# EVALBOARD_001.net
KiCad netlist of a schematic drawn in EAGLE
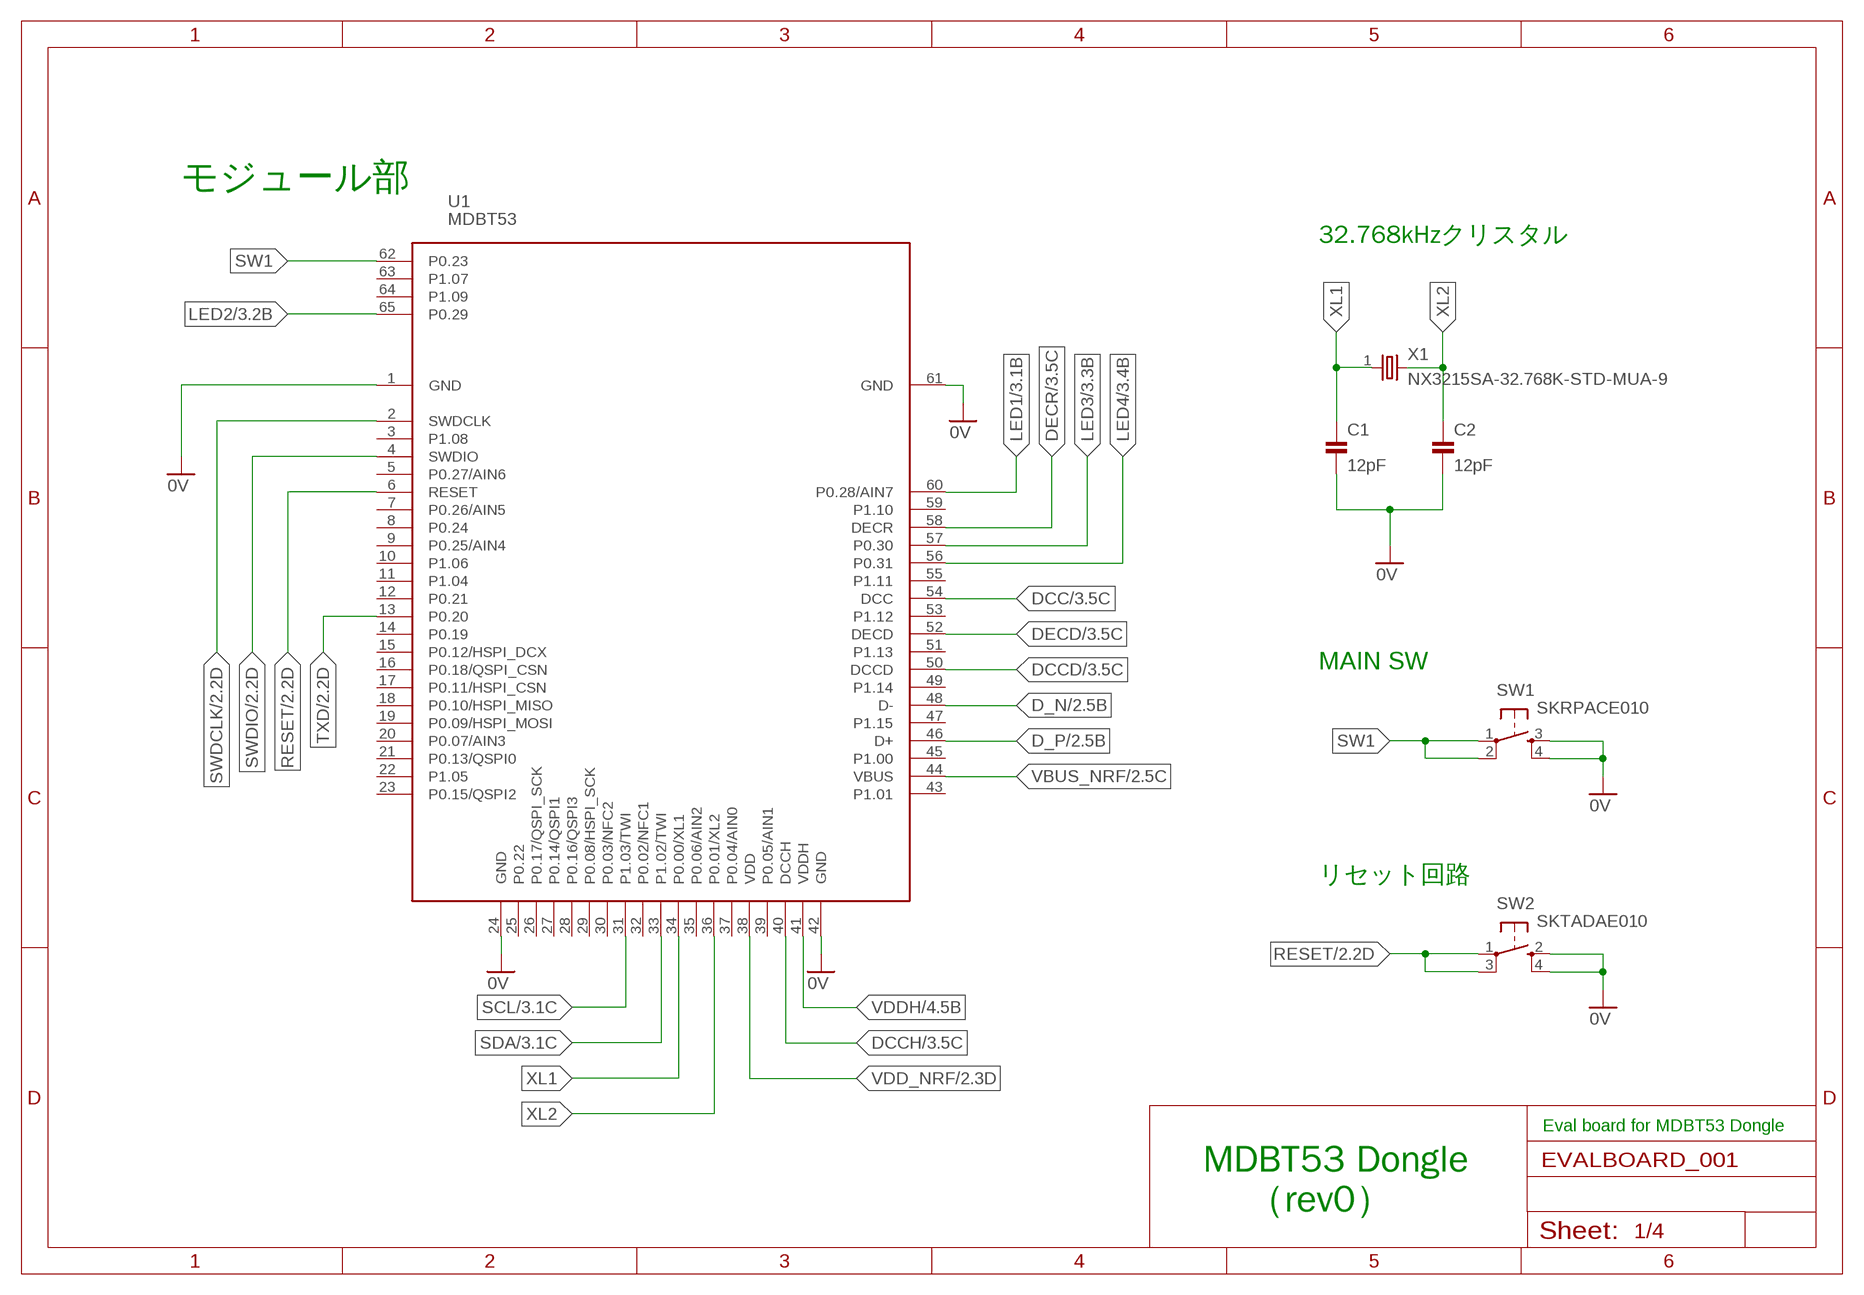
[diagram p0: schematic, sheet 1]
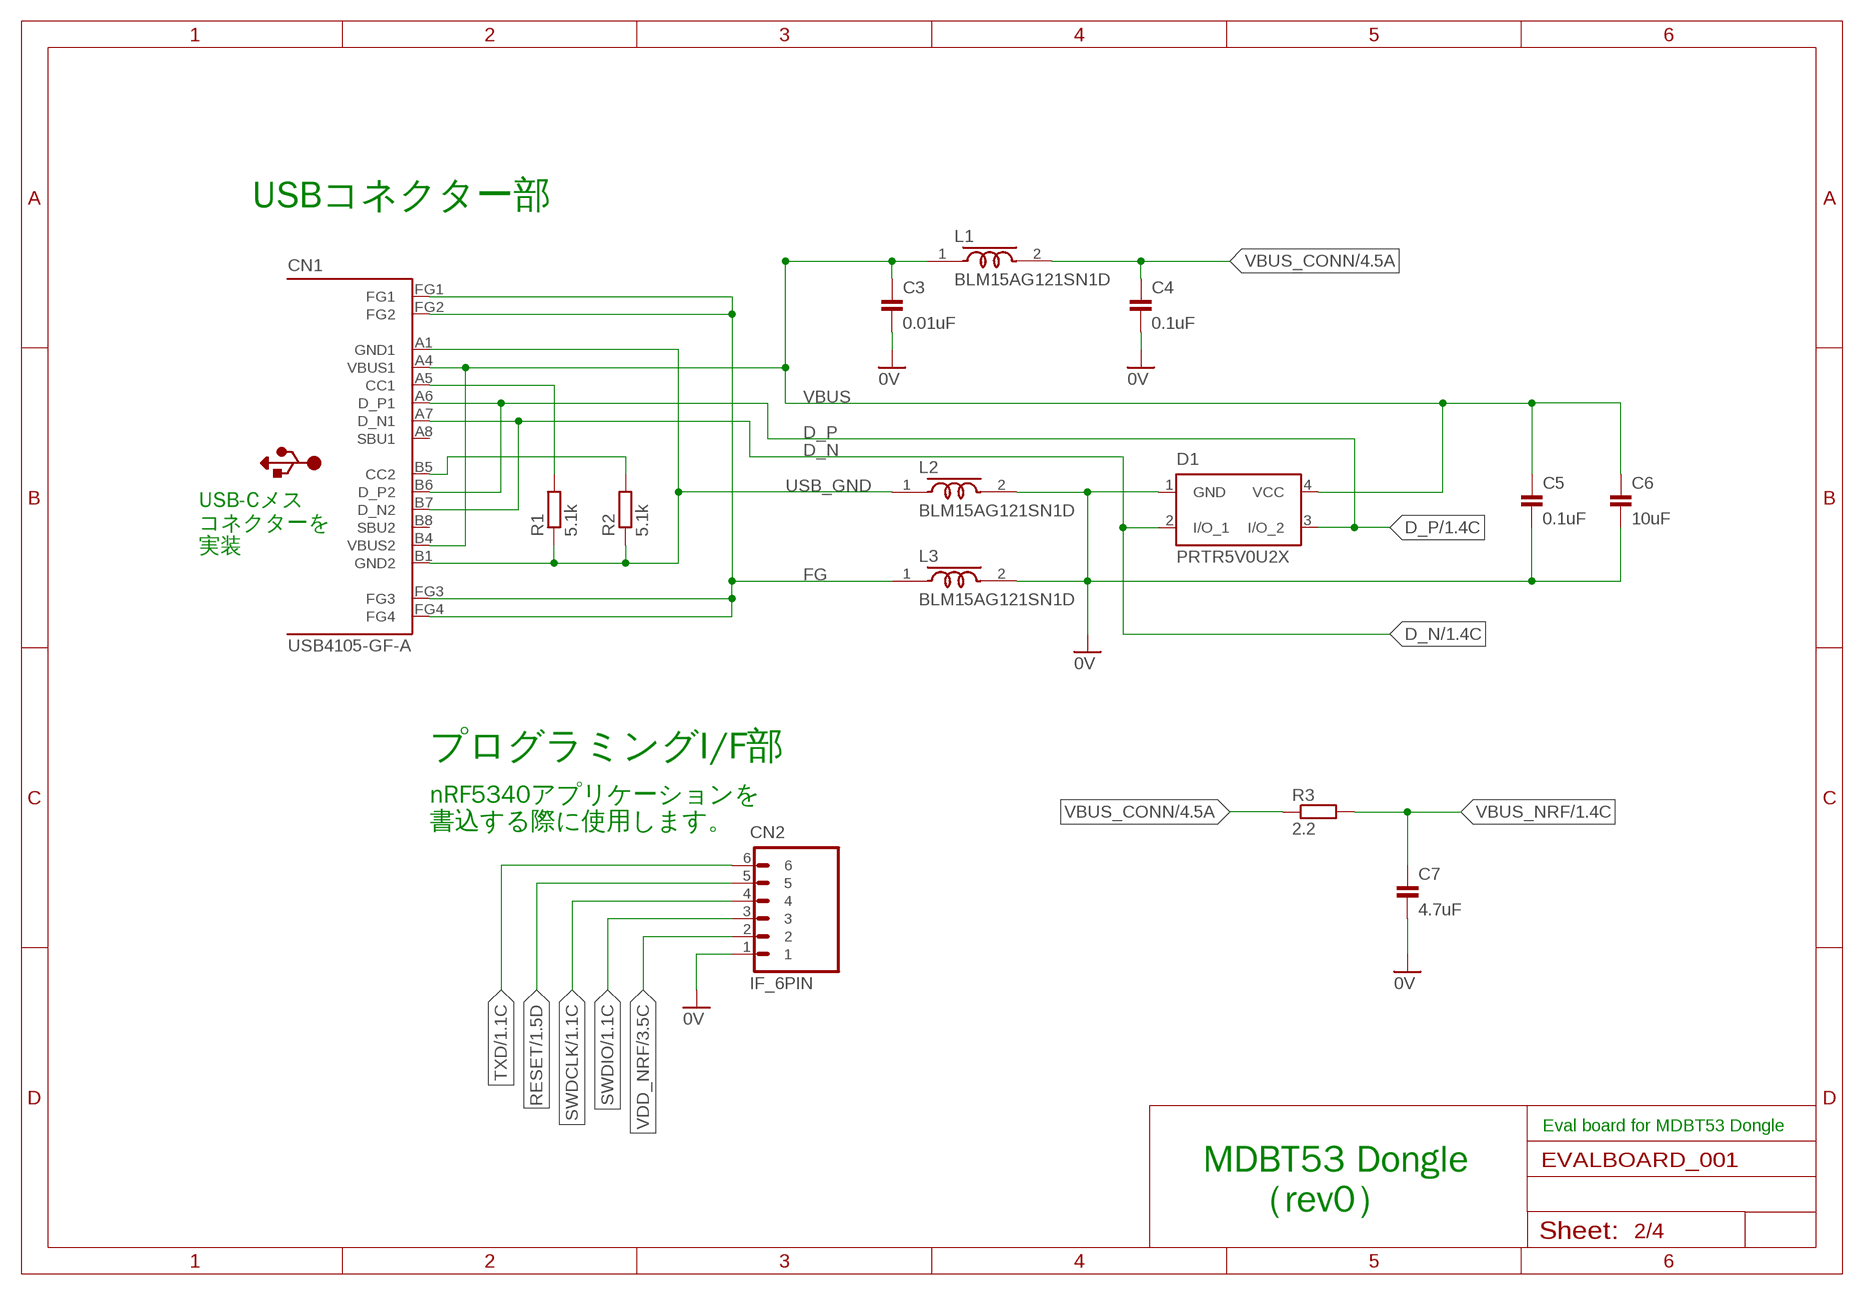
[diagram p1: schematic, sheet 2]
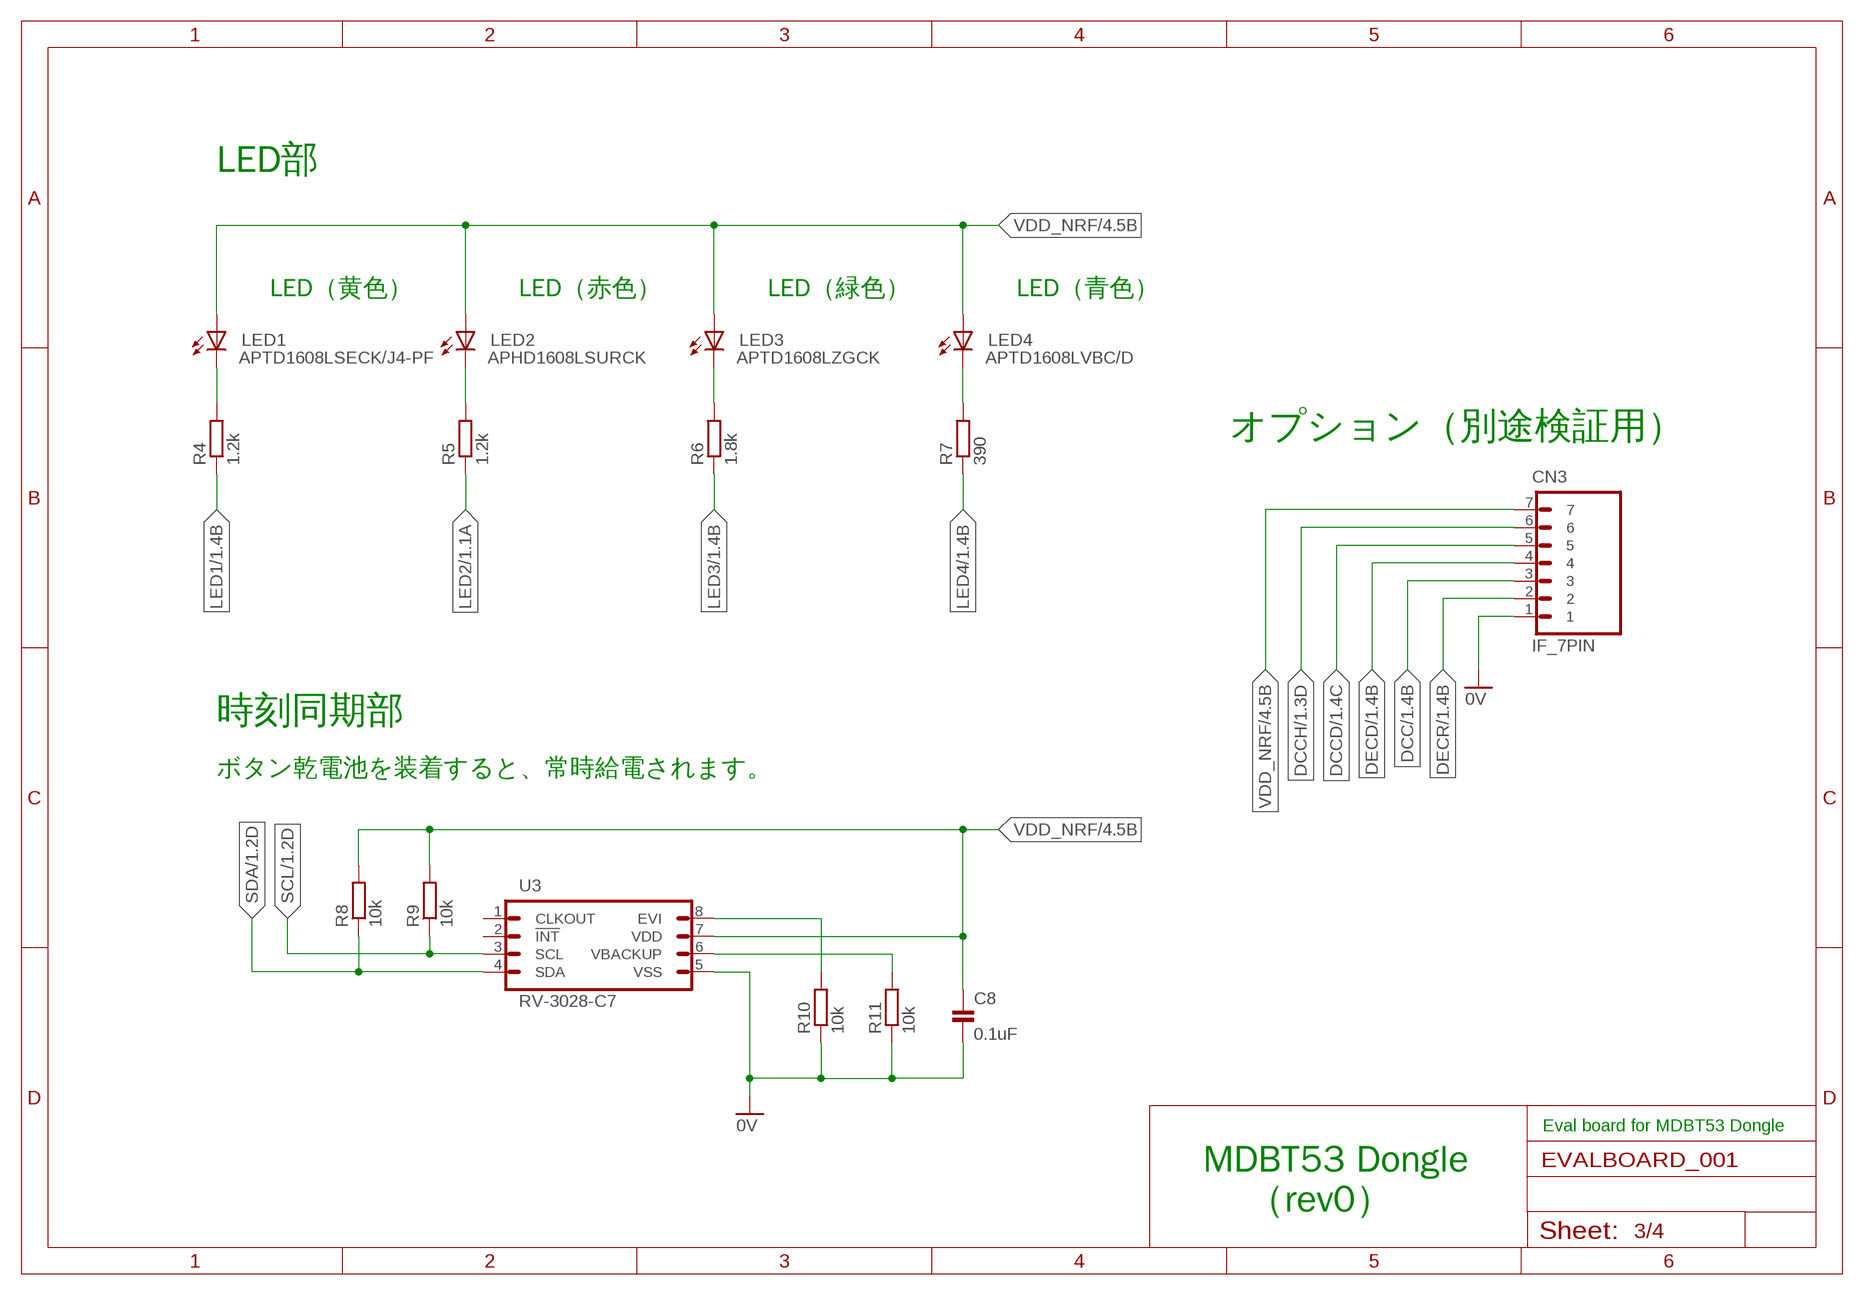
[diagram p2: schematic, sheet 3]
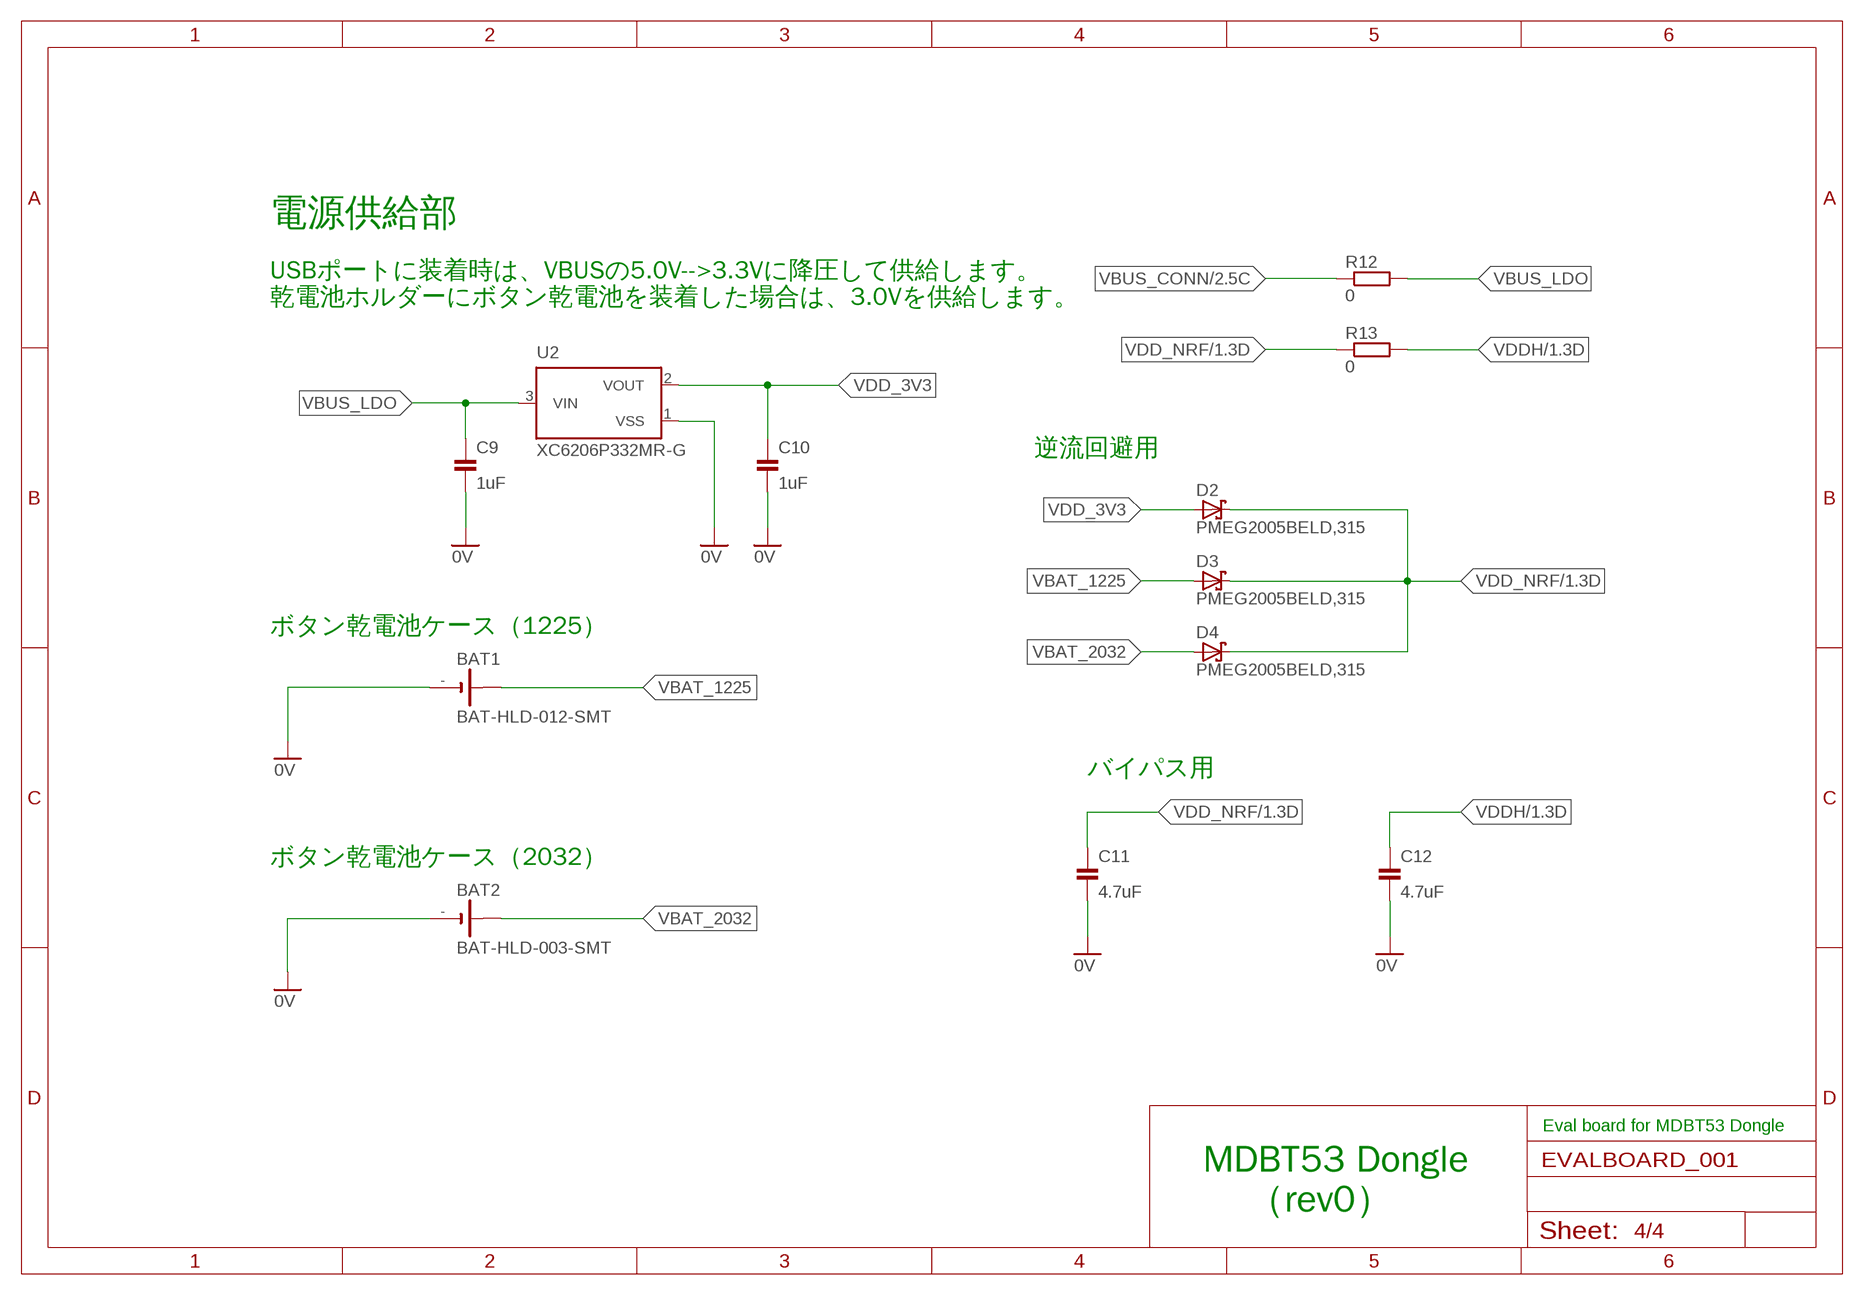
[diagram p3: schematic, sheet 4]

(export (version "E")
  (design (tool "Eeschema 10.0.6"))
  (components
    (comp (ref "BAT1")
      (value "BAT-HLD-012-SMT")
      (footprint "eagle-import:BAT-HLD-012-SMT")
      (libsource (lib "eagle-import") (part "BAT-HLD-012-SMT"))
    )
    (comp (ref "BAT2")
      (value "BAT-HLD-003-SMT")
      (footprint "eagle-import:BAT-HLD-003-SMT")
      (libsource (lib "eagle-import") (part "BAT-HLD-003-SMT"))
    )
    (comp (ref "C9")
      (value "1uF")
      (footprint "eagle-import:C0603K")
      (libsource (lib "eagle-import") (part "CAP_0603"))
    )
    (comp (ref "C10")
      (value "1uF")
      (footprint "eagle-import:C0603K")
      (libsource (lib "eagle-import") (part "CAP_0603"))
    )
    (comp (ref "C11")
      (value "4.7uF")
      (footprint "eagle-import:C0603K")
      (libsource (lib "eagle-import") (part "CAP_0603"))
    )
    (comp (ref "C12")
      (value "4.7uF")
      (footprint "eagle-import:C0603K")
      (libsource (lib "eagle-import") (part "CAP_0603"))
    )
    (comp (ref "D2")
      (value "PMEG2005BELD,315")
      (footprint "eagle-import:DFN1006D-2")
      (libsource (lib "eagle-import") (part "PMEG2005BELD,315"))
    )
    (comp (ref "D3")
      (value "PMEG2005BELD,315")
      (footprint "eagle-import:DFN1006D-2")
      (libsource (lib "eagle-import") (part "PMEG2005BELD,315"))
    )
    (comp (ref "D4")
      (value "PMEG2005BELD,315")
      (footprint "eagle-import:DFN1006D-2")
      (libsource (lib "eagle-import") (part "PMEG2005BELD,315"))
    )
    (comp (ref "R12")
      (value "0")
      (footprint "eagle-import:R0603")
      (libsource (lib "eagle-import") (part "RESISTOR_0603"))
    )
    (comp (ref "R13")
      (value "0")
      (footprint "eagle-import:R0603")
      (libsource (lib "eagle-import") (part "RESISTOR_0603"))
    )
    (comp (ref "U2")
      (value "XC6206P332MR-G")
      (footprint "eagle-import:SOT23")
      (libsource (lib "eagle-import") (part "XC6206P332MR-G"))
    )
    (comp (ref "C3")
      (value "0.01uF")
      (footprint "eagle-import:C0402K")
      (libsource (lib "eagle-import") (part "CAP_0402K"))
    )
    (comp (ref "C4")
      (value "0.1uF")
      (footprint "eagle-import:C0402K")
      (libsource (lib "eagle-import") (part "CAP_0402K"))
    )
    (comp (ref "C5")
      (value "0.1uF")
      (footprint "eagle-import:C0402K")
      (libsource (lib "eagle-import") (part "CAP_0402K"))
    )
    (comp (ref "C6")
      (value "10uF")
      (footprint "eagle-import:C0603K")
      (libsource (lib "eagle-import") (part "CAP_0603"))
    )
    (comp (ref "C7")
      (value "4.7uF")
      (footprint "eagle-import:C0603K")
      (libsource (lib "eagle-import") (part "CAP_0603"))
    )
    (comp (ref "CN1")
      (value "USB4105-GF-A")
      (footprint "eagle-import:USB4105-GF-A")
      (libsource (lib "eagle-import") (part "USB4105-GF-A"))
    )
    (comp (ref "CN2")
      (value "IF_6PIN")
      (footprint "eagle-import:HEADER_6PIN")
      (libsource (lib "eagle-import") (part "IF_6PIN"))
    )
    (comp (ref "D1")
      (value "PRTR5V0U2X")
      (footprint "eagle-import:SOT143B")
      (libsource (lib "eagle-import") (part "PRTR5V0U2X"))
    )
    (comp (ref "L1")
      (value "BLM15AG121SN1D")
      (footprint "eagle-import:C0402K")
      (libsource (lib "eagle-import") (part "BLM15AG121SN1D"))
    )
    (comp (ref "L2")
      (value "BLM15AG121SN1D")
      (footprint "eagle-import:C0402K")
      (libsource (lib "eagle-import") (part "BLM15AG121SN1D"))
    )
    (comp (ref "L3")
      (value "BLM15AG121SN1D")
      (footprint "eagle-import:C0402K")
      (libsource (lib "eagle-import") (part "BLM15AG121SN1D"))
    )
    (comp (ref "R1")
      (value "5.1k")
      (footprint "eagle-import:R0402N")
      (libsource (lib "eagle-import") (part "RESISTOR_0402N"))
    )
    (comp (ref "R2")
      (value "5.1k")
      (footprint "eagle-import:R0402N")
      (libsource (lib "eagle-import") (part "RESISTOR_0402N"))
    )
    (comp (ref "R3")
      (value "2.2")
      (footprint "eagle-import:R0402")
      (libsource (lib "eagle-import") (part "RESISTOR_0402"))
    )
    (comp (ref "C8")
      (value "0.1uF")
      (footprint "eagle-import:C0402K")
      (libsource (lib "eagle-import") (part "CAP_0402K"))
    )
    (comp (ref "CN3")
      (value "IF_7PIN")
      (footprint "eagle-import:HEADER_7PIN")
      (libsource (lib "eagle-import") (part "IF_7PIN"))
    )
    (comp (ref "LED1")
      (value "APTD1608LSECK/J4-PF")
      (footprint "eagle-import:APTD1608")
      (libsource (lib "eagle-import") (part "APTD1608LSECK/J4-PF"))
    )
    (comp (ref "LED2")
      (value "APHD1608LSURCK")
      (footprint "eagle-import:APTD1608")
      (libsource (lib "eagle-import") (part "APHD1608LSURCK"))
    )
    (comp (ref "LED3")
      (value "APTD1608LZGCK")
      (footprint "eagle-import:APTD1608")
      (libsource (lib "eagle-import") (part "APTD1608LZGCK"))
    )
    (comp (ref "LED4")
      (value "APTD1608LVBC/D")
      (footprint "eagle-import:APTD1608")
      (libsource (lib "eagle-import") (part "APTD1608LVBC/D"))
    )
    (comp (ref "R4")
      (value "1.2k")
      (footprint "eagle-import:R0402N")
      (libsource (lib "eagle-import") (part "RESISTOR_0402N"))
    )
    (comp (ref "R5")
      (value "1.2k")
      (footprint "eagle-import:R0402N")
      (libsource (lib "eagle-import") (part "RESISTOR_0402N"))
    )
    (comp (ref "R6")
      (value "1.8k")
      (footprint "eagle-import:R0402N")
      (libsource (lib "eagle-import") (part "RESISTOR_0402N"))
    )
    (comp (ref "R7")
      (value "390")
      (footprint "eagle-import:R0402N")
      (libsource (lib "eagle-import") (part "RESISTOR_0402N"))
    )
    (comp (ref "R8")
      (value "10k")
      (footprint "eagle-import:R0402N")
      (libsource (lib "eagle-import") (part "RESISTOR_0402N"))
    )
    (comp (ref "R9")
      (value "10k")
      (footprint "eagle-import:R0402N")
      (libsource (lib "eagle-import") (part "RESISTOR_0402N"))
    )
    (comp (ref "R10")
      (value "10k")
      (footprint "eagle-import:R0402N")
      (libsource (lib "eagle-import") (part "RESISTOR_0402N"))
    )
    (comp (ref "R11")
      (value "10k")
      (footprint "eagle-import:R0402N")
      (libsource (lib "eagle-import") (part "RESISTOR_0402N"))
    )
    (comp (ref "U3")
      (value "RV-3028-C7")
      (footprint "eagle-import:SON-8")
      (libsource (lib "eagle-import") (part "RV-3028-C7"))
    )
    (comp (ref "C1")
      (value "12pF")
      (footprint "eagle-import:C0603K")
      (libsource (lib "eagle-import") (part "CAP_0603"))
    )
    (comp (ref "C2")
      (value "12pF")
      (footprint "eagle-import:C0603K")
      (libsource (lib "eagle-import") (part "CAP_0603"))
    )
    (comp (ref "SW1")
      (value "SKRPACE010")
      (footprint "eagle-import:SKRPACE010")
      (libsource (lib "eagle-import") (part "SKRPACE010"))
    )
    (comp (ref "SW2")
      (value "SKTADAE010")
      (footprint "eagle-import:SKTADAE010")
      (libsource (lib "eagle-import") (part "SKTADAE010"))
    )
    (comp (ref "U1")
      (value "MDBT53")
      (footprint "eagle-import:MDBT53")
      (libsource (lib "eagle-import") (part "MDBT53"))
    )
    (comp (ref "X1")
      (value "NX3215SA-32.768K-STD-MUA-9")
      (footprint "eagle-import:NX3215")
      (libsource (lib "eagle-import") (part "NX3215SA-32.768K-STD-MUA-9"))
    )
  )
  (nets
    (net (code "1") (name "0V") (class "Default")
      (node (ref "BAT1") (pin "-") (pinfunction "-_-") (pintype "passive"))
      (node (ref "BAT2") (pin "-") (pinfunction "-_-") (pintype "passive"))
      (node (ref "C1") (pin "2") (pinfunction "2_2") (pintype "passive"))
      (node (ref "C10") (pin "2") (pinfunction "2_2") (pintype "passive"))
      (node (ref "C11") (pin "2") (pinfunction "2_2") (pintype "passive"))
      (node (ref "C12") (pin "2") (pinfunction "2_2") (pintype "passive"))
      (node (ref "C2") (pin "2") (pinfunction "2_2") (pintype "passive"))
      (node (ref "C3") (pin "2") (pinfunction "2_2") (pintype "passive"))
      (node (ref "C4") (pin "2") (pinfunction "2_2") (pintype "passive"))
      (node (ref "C5") (pin "2") (pinfunction "2_2") (pintype "passive"))
      (node (ref "C6") (pin "2") (pinfunction "2_2") (pintype "passive"))
      (node (ref "C7") (pin "2") (pinfunction "2_2") (pintype "passive"))
      (node (ref "C8") (pin "2") (pinfunction "2_2") (pintype "passive"))
      (node (ref "C9") (pin "2") (pinfunction "2_2") (pintype "passive"))
      (node (ref "CN2") (pin "1") (pinfunction "1_1") (pintype "passive"))
      (node (ref "CN3") (pin "1") (pinfunction "1_1") (pintype "passive"))
      (node (ref "D1") (pin "1") (pinfunction "GND_1") (pintype "passive"))
      (node (ref "L2") (pin "2") (pinfunction "2_2") (pintype "passive"))
      (node (ref "L3") (pin "2") (pinfunction "2_2") (pintype "passive"))
      (node (ref "R10") (pin "1") (pinfunction "1_1") (pintype "passive"))
      (node (ref "R11") (pin "1") (pinfunction "1_1") (pintype "passive"))
      (node (ref "SW1") (pin "3") (pinfunction "S_3") (pintype "passive"))
      (node (ref "SW1") (pin "4") (pinfunction "S1_4") (pintype "passive"))
      (node (ref "SW2") (pin "2") (pinfunction "S_2") (pintype "passive"))
      (node (ref "SW2") (pin "4") (pinfunction "S1_4") (pintype "passive"))
      (node (ref "U1") (pin "1") (pinfunction "GND_1") (pintype "bidirectional"))
      (node (ref "U1") (pin "24") (pinfunction "GND_24") (pintype "bidirectional"))
      (node (ref "U1") (pin "42") (pinfunction "GND_42") (pintype "bidirectional"))
      (node (ref "U1") (pin "61") (pinfunction "GND_61") (pintype "bidirectional"))
      (node (ref "U2") (pin "1") (pinfunction "VSS_1") (pintype "passive"))
      (node (ref "U3") (pin "5") (pinfunction "VSS_5") (pintype "passive"))
    )
    (net (code "2") (name "DCC") (class "Default")
      (node (ref "CN3") (pin "3") (pinfunction "3_3") (pintype "passive"))
      (node (ref "U1") (pin "54") (pinfunction "DCC_54") (pintype "bidirectional"))
    )
    (net (code "3") (name "DCCD") (class "Default")
      (node (ref "CN3") (pin "5") (pinfunction "5_5") (pintype "passive"))
      (node (ref "U1") (pin "50") (pinfunction "DCCD_50") (pintype "bidirectional"))
    )
    (net (code "4") (name "DCCH") (class "Default")
      (node (ref "CN3") (pin "6") (pinfunction "6_6") (pintype "passive"))
      (node (ref "U1") (pin "40") (pinfunction "DCCH_40") (pintype "bidirectional"))
    )
    (net (code "5") (name "DECD") (class "Default")
      (node (ref "CN3") (pin "4") (pinfunction "4_4") (pintype "passive"))
      (node (ref "U1") (pin "52") (pinfunction "DECD_52") (pintype "bidirectional"))
    )
    (net (code "6") (name "DECR") (class "Default")
      (node (ref "CN3") (pin "2") (pinfunction "2_2") (pintype "passive"))
      (node (ref "U1") (pin "58") (pinfunction "DECR_58") (pintype "bidirectional"))
    )
    (net (code "7") (name "D_N") (class "Default")
      (node (ref "CN1") (pin "A7") (pinfunction "D_N1_A7") (pintype "bidirectional"))
      (node (ref "CN1") (pin "B7") (pinfunction "D_N2_B7") (pintype "bidirectional"))
      (node (ref "D1") (pin "2") (pinfunction "I/O_1_2") (pintype "bidirectional"))
      (node (ref "U1") (pin "48") (pinfunction "D-_48") (pintype "bidirectional"))
    )
    (net (code "8") (name "D_P") (class "Default")
      (node (ref "CN1") (pin "A6") (pinfunction "D_P1_A6") (pintype "bidirectional"))
      (node (ref "CN1") (pin "B6") (pinfunction "D_P2_B6") (pintype "bidirectional"))
      (node (ref "D1") (pin "3") (pinfunction "I/O_2_3") (pintype "bidirectional"))
      (node (ref "U1") (pin "46") (pinfunction "D+_46") (pintype "bidirectional"))
    )
    (net (code "9") (name "FG") (class "Default")
      (node (ref "CN1") (pin "FG1") (pinfunction "FG1_FG1") (pintype "passive"))
      (node (ref "CN1") (pin "FG2") (pinfunction "FG2_FG2") (pintype "bidirectional"))
      (node (ref "CN1") (pin "FG3") (pinfunction "FG3_FG3") (pintype "passive"))
      (node (ref "CN1") (pin "FG4") (pinfunction "FG4_FG4") (pintype "passive"))
      (node (ref "L3") (pin "1") (pinfunction "1_1") (pintype "passive"))
    )
    (net (code "10") (name "LED1") (class "Default")
      (node (ref "R4") (pin "1") (pinfunction "1_1") (pintype "passive"))
      (node (ref "U1") (pin "60") (pinfunction "P0.28/AIN7_60") (pintype "bidirectional"))
    )
    (net (code "11") (name "LED2") (class "Default")
      (node (ref "R5") (pin "1") (pinfunction "1_1") (pintype "passive"))
      (node (ref "U1") (pin "65") (pinfunction "P0.29_65") (pintype "bidirectional"))
    )
    (net (code "12") (name "LED3") (class "Default")
      (node (ref "R6") (pin "1") (pinfunction "1_1") (pintype "passive"))
      (node (ref "U1") (pin "57") (pinfunction "P0.30_57") (pintype "bidirectional"))
    )
    (net (code "13") (name "LED4") (class "Default")
      (node (ref "R7") (pin "1") (pinfunction "1_1") (pintype "passive"))
      (node (ref "U1") (pin "56") (pinfunction "P0.31_56") (pintype "bidirectional"))
    )
    (net (code "14") (name "Net-(CN1-CC1)") (class "Default")
      (node (ref "CN1") (pin "A5") (pinfunction "CC1_A5") (pintype "passive"))
      (node (ref "R1") (pin "2") (pinfunction "2_2") (pintype "passive"))
    )
    (net (code "15") (name "Net-(CN1-CC2)") (class "Default")
      (node (ref "CN1") (pin "B5") (pinfunction "CC2_B5") (pintype "passive"))
      (node (ref "R2") (pin "2") (pinfunction "2_2") (pintype "passive"))
    )
    (net (code "16") (name "Net-(LED1-PadC)") (class "Default")
      (node (ref "LED1") (pin "C") (pinfunction "C_C") (pintype "passive"))
      (node (ref "R4") (pin "2") (pinfunction "2_2") (pintype "passive"))
    )
    (net (code "17") (name "Net-(LED2-PadC)") (class "Default")
      (node (ref "LED2") (pin "C") (pinfunction "C_C") (pintype "passive"))
      (node (ref "R5") (pin "2") (pinfunction "2_2") (pintype "passive"))
    )
    (net (code "18") (name "Net-(LED3-PadC)") (class "Default")
      (node (ref "LED3") (pin "C") (pinfunction "C_C") (pintype "passive"))
      (node (ref "R6") (pin "2") (pinfunction "2_2") (pintype "passive"))
    )
    (net (code "19") (name "Net-(LED4-PadC)") (class "Default")
      (node (ref "LED4") (pin "C") (pinfunction "C_C") (pintype "passive"))
      (node (ref "R7") (pin "2") (pinfunction "2_2") (pintype "passive"))
    )
    (net (code "20") (name "Net-(U3-EVI)") (class "Default")
      (node (ref "R10") (pin "2") (pinfunction "2_2") (pintype "passive"))
      (node (ref "U3") (pin "8") (pinfunction "EVI_8") (pintype "bidirectional"))
    )
    (net (code "21") (name "Net-(U3-VBACKUP)") (class "Default")
      (node (ref "R11") (pin "2") (pinfunction "2_2") (pintype "passive"))
      (node (ref "U3") (pin "6") (pinfunction "VBACKUP_6") (pintype "passive"))
    )
    (net (code "22") (name "RESET") (class "Default")
      (node (ref "CN2") (pin "5") (pinfunction "5_5") (pintype "passive"))
      (node (ref "SW2") (pin "1") (pinfunction "P_1") (pintype "passive"))
      (node (ref "SW2") (pin "3") (pinfunction "P1_3") (pintype "passive"))
      (node (ref "U1") (pin "6") (pinfunction "RESET_6") (pintype "bidirectional"))
    )
    (net (code "23") (name "SCL") (class "Default")
      (node (ref "R9") (pin "1") (pinfunction "1_1") (pintype "passive"))
      (node (ref "U1") (pin "31") (pinfunction "P1.03/TWI_31") (pintype "bidirectional"))
      (node (ref "U3") (pin "3") (pinfunction "SCL_3") (pintype "bidirectional"))
    )
    (net (code "24") (name "SDA") (class "Default")
      (node (ref "R8") (pin "1") (pinfunction "1_1") (pintype "passive"))
      (node (ref "U1") (pin "33") (pinfunction "P1.02/TWI_33") (pintype "bidirectional"))
      (node (ref "U3") (pin "4") (pinfunction "SDA_4") (pintype "bidirectional"))
    )
    (net (code "25") (name "SW1") (class "Default")
      (node (ref "SW1") (pin "1") (pinfunction "P_1") (pintype "passive"))
      (node (ref "SW1") (pin "2") (pinfunction "P1_2") (pintype "passive"))
      (node (ref "U1") (pin "62") (pinfunction "P0.23_62") (pintype "bidirectional"))
    )
    (net (code "26") (name "SWDCLK") (class "Default")
      (node (ref "CN2") (pin "4") (pinfunction "4_4") (pintype "passive"))
      (node (ref "U1") (pin "2") (pinfunction "SWDCLK_2") (pintype "bidirectional"))
    )
    (net (code "27") (name "SWDIO") (class "Default")
      (node (ref "CN2") (pin "3") (pinfunction "3_3") (pintype "passive"))
      (node (ref "U1") (pin "4") (pinfunction "SWDIO_4") (pintype "bidirectional"))
    )
    (net (code "28") (name "TXD") (class "Default")
      (node (ref "CN2") (pin "6") (pinfunction "6_6") (pintype "passive"))
      (node (ref "U1") (pin "13") (pinfunction "P0.20_13") (pintype "bidirectional"))
    )
    (net (code "29") (name "USB_GND") (class "Default")
      (node (ref "CN1") (pin "A1") (pinfunction "GND1_A1") (pintype "passive"))
      (node (ref "CN1") (pin "B1") (pinfunction "GND2_B1") (pintype "passive"))
      (node (ref "L2") (pin "1") (pinfunction "1_1") (pintype "passive"))
      (node (ref "R1") (pin "1") (pinfunction "1_1") (pintype "passive"))
      (node (ref "R2") (pin "1") (pinfunction "1_1") (pintype "passive"))
    )
    (net (code "30") (name "VBAT_1225") (class "Default")
      (node (ref "BAT1") (pin "+@2") (pinfunction "+_+@2") (pintype "passive"))
      (node (ref "D3") (pin "2") (pinfunction "A_2") (pintype "passive"))
    )
    (net (code "31") (name "VBAT_2032") (class "Default")
      (node (ref "BAT2") (pin "+@1") (pinfunction "+_+@1") (pintype "passive"))
      (node (ref "D4") (pin "2") (pinfunction "A_2") (pintype "passive"))
    )
    (net (code "32") (name "VBUS") (class "Default")
      (node (ref "C3") (pin "1") (pinfunction "1_1") (pintype "passive"))
      (node (ref "C5") (pin "1") (pinfunction "1_1") (pintype "passive"))
      (node (ref "C6") (pin "1") (pinfunction "1_1") (pintype "passive"))
      (node (ref "CN1") (pin "A4") (pinfunction "VBUS1_A4") (pintype "passive"))
      (node (ref "CN1") (pin "B4") (pinfunction "VBUS2_B4") (pintype "passive"))
      (node (ref "D1") (pin "4") (pinfunction "VCC_4") (pintype "passive"))
      (node (ref "L1") (pin "1") (pinfunction "1_1") (pintype "passive"))
    )
    (net (code "33") (name "VBUS_CONN") (class "Default")
      (node (ref "C4") (pin "1") (pinfunction "1_1") (pintype "passive"))
      (node (ref "L1") (pin "2") (pinfunction "2_2") (pintype "passive"))
      (node (ref "R12") (pin "1") (pinfunction "1_1") (pintype "passive"))
      (node (ref "R3") (pin "1") (pinfunction "1_1") (pintype "passive"))
    )
    (net (code "34") (name "VBUS_LDO") (class "Default")
      (node (ref "C9") (pin "1") (pinfunction "1_1") (pintype "passive"))
      (node (ref "R12") (pin "2") (pinfunction "2_2") (pintype "passive"))
      (node (ref "U2") (pin "3") (pinfunction "VIN_3") (pintype "passive"))
    )
    (net (code "35") (name "VBUS_NRF") (class "Default")
      (node (ref "C7") (pin "1") (pinfunction "1_1") (pintype "passive"))
      (node (ref "R3") (pin "2") (pinfunction "2_2") (pintype "passive"))
      (node (ref "U1") (pin "44") (pinfunction "VBUS_44") (pintype "bidirectional"))
    )
    (net (code "36") (name "VDDH") (class "Default")
      (node (ref "C12") (pin "1") (pinfunction "1_1") (pintype "passive"))
      (node (ref "R13") (pin "2") (pinfunction "2_2") (pintype "passive"))
      (node (ref "U1") (pin "41") (pinfunction "VDDH_41") (pintype "bidirectional"))
    )
    (net (code "37") (name "VDD_3V3") (class "Default")
      (node (ref "C10") (pin "1") (pinfunction "1_1") (pintype "passive"))
      (node (ref "D2") (pin "2") (pinfunction "A_2") (pintype "passive"))
      (node (ref "U2") (pin "2") (pinfunction "VOUT_2") (pintype "passive"))
    )
    (net (code "38") (name "VDD_NRF") (class "Default")
      (node (ref "C11") (pin "1") (pinfunction "1_1") (pintype "passive"))
      (node (ref "C8") (pin "1") (pinfunction "1_1") (pintype "passive"))
      (node (ref "CN2") (pin "2") (pinfunction "2_2") (pintype "passive"))
      (node (ref "CN3") (pin "7") (pinfunction "7_7") (pintype "passive"))
      (node (ref "D2") (pin "1") (pinfunction "C_1") (pintype "passive"))
      (node (ref "D3") (pin "1") (pinfunction "C_1") (pintype "passive"))
      (node (ref "D4") (pin "1") (pinfunction "C_1") (pintype "passive"))
      (node (ref "LED1") (pin "A") (pinfunction "A_A") (pintype "passive"))
      (node (ref "LED2") (pin "A") (pinfunction "A_A") (pintype "passive"))
      (node (ref "LED3") (pin "A") (pinfunction "A_A") (pintype "passive"))
      (node (ref "LED4") (pin "A") (pinfunction "A_A") (pintype "passive"))
      (node (ref "R13") (pin "1") (pinfunction "1_1") (pintype "passive"))
      (node (ref "R8") (pin "2") (pinfunction "2_2") (pintype "passive"))
      (node (ref "R9") (pin "2") (pinfunction "2_2") (pintype "passive"))
      (node (ref "U1") (pin "38") (pinfunction "VDD_38") (pintype "bidirectional"))
      (node (ref "U3") (pin "7") (pinfunction "VDD_7") (pintype "passive"))
    )
    (net (code "39") (name "XL1") (class "Default")
      (node (ref "C1") (pin "1") (pinfunction "1_1") (pintype "passive"))
      (node (ref "U1") (pin "34") (pinfunction "P0.00/XL1_34") (pintype "bidirectional"))
      (node (ref "X1") (pin "1") (pinfunction "1_1") (pintype "passive"))
    )
    (net (code "40") (name "XL2") (class "Default")
      (node (ref "C2") (pin "1") (pinfunction "1_1") (pintype "passive"))
      (node (ref "U1") (pin "36") (pinfunction "P0.01/XL2_36") (pintype "bidirectional"))
      (node (ref "X1") (pin "2") (pinfunction "2_2") (pintype "passive"))
    )
    (net (code "41") (name "unconnected-(CN1-SBU1-PadA8)") (class "Default")
      (node (ref "CN1") (pin "A8") (pinfunction "SBU1_A8") (pintype "passive"))
    )
    (net (code "42") (name "unconnected-(CN1-SBU2-PadB8)") (class "Default")
      (node (ref "CN1") (pin "B8") (pinfunction "SBU2_B8") (pintype "passive"))
    )
    (net (code "43") (name "unconnected-(U1-P0.02{slash}NFC1-Pad32)") (class "Default")
      (node (ref "U1") (pin "32") (pinfunction "P0.02/NFC1_32") (pintype "bidirectional"))
    )
    (net (code "44") (name "unconnected-(U1-P0.03{slash}NFC2-Pad30)") (class "Default")
      (node (ref "U1") (pin "30") (pinfunction "P0.03/NFC2_30") (pintype "bidirectional"))
    )
    (net (code "45") (name "unconnected-(U1-P0.04{slash}AIN0-Pad37)") (class "Default")
      (node (ref "U1") (pin "37") (pinfunction "P0.04/AIN0_37") (pintype "bidirectional"))
    )
    (net (code "46") (name "unconnected-(U1-P0.05{slash}AIN1-Pad39)") (class "Default")
      (node (ref "U1") (pin "39") (pinfunction "P0.05/AIN1_39") (pintype "bidirectional"))
    )
    (net (code "47") (name "unconnected-(U1-P0.06{slash}AIN2-Pad35)") (class "Default")
      (node (ref "U1") (pin "35") (pinfunction "P0.06/AIN2_35") (pintype "bidirectional"))
    )
    (net (code "48") (name "unconnected-(U1-P0.07{slash}AIN3-Pad20)") (class "Default")
      (node (ref "U1") (pin "20") (pinfunction "P0.07/AIN3_20") (pintype "bidirectional"))
    )
    (net (code "49") (name "unconnected-(U1-P0.08{slash}HSPI_SCK-Pad29)") (class "Default")
      (node (ref "U1") (pin "29") (pinfunction "P0.08/HSPI_SCK_29") (pintype "bidirectional"))
    )
    (net (code "50") (name "unconnected-(U1-P0.09{slash}HSPI_MOSI-Pad19)") (class "Default")
      (node (ref "U1") (pin "19") (pinfunction "P0.09/HSPI_MOSI_19") (pintype "bidirectional"))
    )
    (net (code "51") (name "unconnected-(U1-P0.10{slash}HSPI_MISO-Pad18)") (class "Default")
      (node (ref "U1") (pin "18") (pinfunction "P0.10/HSPI_MISO_18") (pintype "bidirectional"))
    )
    (net (code "52") (name "unconnected-(U1-P0.11{slash}HSPI_CSN-Pad17)") (class "Default")
      (node (ref "U1") (pin "17") (pinfunction "P0.11/HSPI_CSN_17") (pintype "bidirectional"))
    )
    (net (code "53") (name "unconnected-(U1-P0.12{slash}HSPI_DCX-Pad15)") (class "Default")
      (node (ref "U1") (pin "15") (pinfunction "P0.12/HSPI_DCX_15") (pintype "bidirectional"))
    )
    (net (code "54") (name "unconnected-(U1-P0.13{slash}QSPI0-Pad21)") (class "Default")
      (node (ref "U1") (pin "21") (pinfunction "P0.13/QSPI0_21") (pintype "bidirectional"))
    )
    (net (code "55") (name "unconnected-(U1-P0.14{slash}QSPI1-Pad27)") (class "Default")
      (node (ref "U1") (pin "27") (pinfunction "P0.14/QSPI1_27") (pintype "bidirectional"))
    )
    (net (code "56") (name "unconnected-(U1-P0.15{slash}QSPI2-Pad23)") (class "Default")
      (node (ref "U1") (pin "23") (pinfunction "P0.15/QSPI2_23") (pintype "bidirectional"))
    )
    (net (code "57") (name "unconnected-(U1-P0.16{slash}QSPI3-Pad28)") (class "Default")
      (node (ref "U1") (pin "28") (pinfunction "P0.16/QSPI3_28") (pintype "bidirectional"))
    )
    (net (code "58") (name "unconnected-(U1-P0.17{slash}QSPI_SCK-Pad26)") (class "Default")
      (node (ref "U1") (pin "26") (pinfunction "P0.17/QSPI_SCK_26") (pintype "bidirectional"))
    )
    (net (code "59") (name "unconnected-(U1-P0.18{slash}QSPI_CSN-Pad16)") (class "Default")
      (node (ref "U1") (pin "16") (pinfunction "P0.18/QSPI_CSN_16") (pintype "bidirectional"))
    )
    (net (code "60") (name "unconnected-(U1-P0.19-Pad14)") (class "Default")
      (node (ref "U1") (pin "14") (pinfunction "P0.19_14") (pintype "bidirectional"))
    )
    (net (code "61") (name "unconnected-(U1-P0.21-Pad12)") (class "Default")
      (node (ref "U1") (pin "12") (pinfunction "P0.21_12") (pintype "bidirectional"))
    )
    (net (code "62") (name "unconnected-(U1-P0.22-Pad25)") (class "Default")
      (node (ref "U1") (pin "25") (pinfunction "P0.22_25") (pintype "bidirectional"))
    )
    (net (code "63") (name "unconnected-(U1-P0.24-Pad8)") (class "Default")
      (node (ref "U1") (pin "8") (pinfunction "P0.24_8") (pintype "bidirectional"))
    )
    (net (code "64") (name "unconnected-(U1-P0.25{slash}AIN4-Pad9)") (class "Default")
      (node (ref "U1") (pin "9") (pinfunction "P0.25/AIN4_9") (pintype "bidirectional"))
    )
    (net (code "65") (name "unconnected-(U1-P0.26{slash}AIN5-Pad7)") (class "Default")
      (node (ref "U1") (pin "7") (pinfunction "P0.26/AIN5_7") (pintype "bidirectional"))
    )
    (net (code "66") (name "unconnected-(U1-P0.27{slash}AIN6-Pad5)") (class "Default")
      (node (ref "U1") (pin "5") (pinfunction "P0.27/AIN6_5") (pintype "bidirectional"))
    )
    (net (code "67") (name "unconnected-(U1-P1.00-Pad45)") (class "Default")
      (node (ref "U1") (pin "45") (pinfunction "P1.00_45") (pintype "bidirectional"))
    )
    (net (code "68") (name "unconnected-(U1-P1.01-Pad43)") (class "Default")
      (node (ref "U1") (pin "43") (pinfunction "P1.01_43") (pintype "bidirectional"))
    )
    (net (code "69") (name "unconnected-(U1-P1.04-Pad11)") (class "Default")
      (node (ref "U1") (pin "11") (pinfunction "P1.04_11") (pintype "bidirectional"))
    )
    (net (code "70") (name "unconnected-(U1-P1.05-Pad22)") (class "Default")
      (node (ref "U1") (pin "22") (pinfunction "P1.05_22") (pintype "bidirectional"))
    )
    (net (code "71") (name "unconnected-(U1-P1.06-Pad10)") (class "Default")
      (node (ref "U1") (pin "10") (pinfunction "P1.06_10") (pintype "bidirectional"))
    )
    (net (code "72") (name "unconnected-(U1-P1.07-Pad63)") (class "Default")
      (node (ref "U1") (pin "63") (pinfunction "P1.07_63") (pintype "bidirectional"))
    )
    (net (code "73") (name "unconnected-(U1-P1.08-Pad3)") (class "Default")
      (node (ref "U1") (pin "3") (pinfunction "P1.08_3") (pintype "bidirectional"))
    )
    (net (code "74") (name "unconnected-(U1-P1.09-Pad64)") (class "Default")
      (node (ref "U1") (pin "64") (pinfunction "P1.09_64") (pintype "bidirectional"))
    )
    (net (code "75") (name "unconnected-(U1-P1.10-Pad59)") (class "Default")
      (node (ref "U1") (pin "59") (pinfunction "P1.10_59") (pintype "bidirectional"))
    )
    (net (code "76") (name "unconnected-(U1-P1.11-Pad55)") (class "Default")
      (node (ref "U1") (pin "55") (pinfunction "P1.11_55") (pintype "bidirectional"))
    )
    (net (code "77") (name "unconnected-(U1-P1.12-Pad53)") (class "Default")
      (node (ref "U1") (pin "53") (pinfunction "P1.12_53") (pintype "bidirectional"))
    )
    (net (code "78") (name "unconnected-(U1-P1.13-Pad51)") (class "Default")
      (node (ref "U1") (pin "51") (pinfunction "P1.13_51") (pintype "bidirectional"))
    )
    (net (code "79") (name "unconnected-(U1-P1.14-Pad49)") (class "Default")
      (node (ref "U1") (pin "49") (pinfunction "P1.14_49") (pintype "bidirectional"))
    )
    (net (code "80") (name "unconnected-(U1-P1.15-Pad47)") (class "Default")
      (node (ref "U1") (pin "47") (pinfunction "P1.15_47") (pintype "bidirectional"))
    )
    (net (code "81") (name "unconnected-(U3-CLKOUT-Pad1)") (class "Default")
      (node (ref "U3") (pin "1") (pinfunction "CLKOUT_1") (pintype "bidirectional"))
    )
    (net (code "82") (name "unconnected-(U3-~{INT}-Pad2)") (class "Default")
      (node (ref "U3") (pin "2") (pinfunction "~{INT}_2") (pintype "bidirectional"))
    )
  )
)
